# Thermocouple_Test.net
KiCad netlist of a schematic drawn in EAGLE
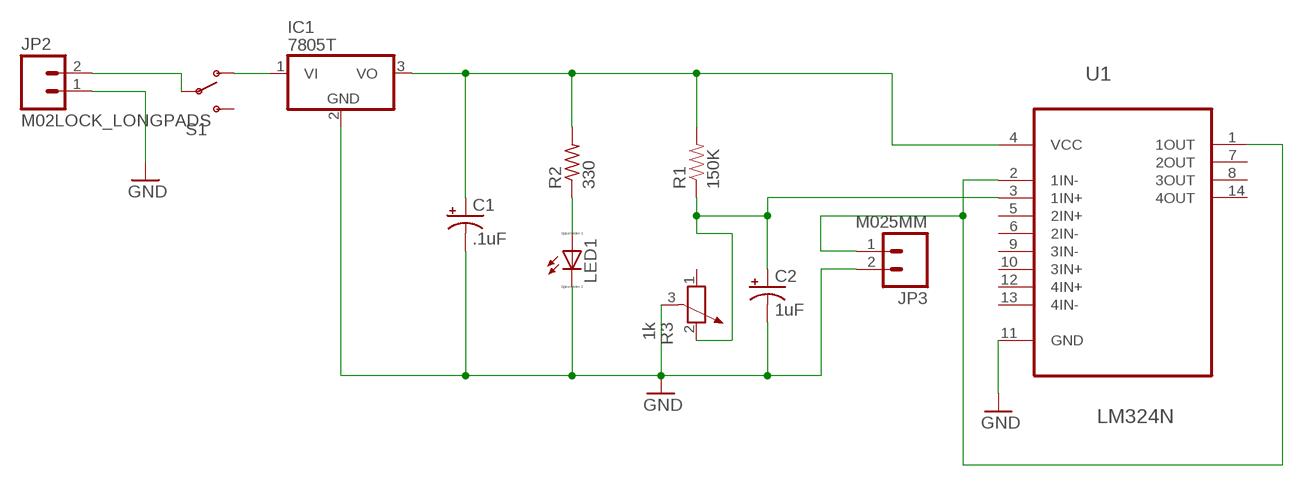
[diagram p0: schematic, sheet 1]

(export (version "E")
  (design (tool "Eeschema 10.0.6"))
  (components
    (comp (ref "C1")
      (value ".1uF")
      (footprint "eagle-import:CPOL-RADIAL-10UF-25V-KIT")
      (libsource (lib "eagle-import") (part "10UF-25V-20%(PTH)KIT"))
    )
    (comp (ref "C2")
      (value "1uF")
      (footprint "eagle-import:CPOL-RADIAL-10UF-25V-KIT")
      (libsource (lib "eagle-import") (part "10UF-25V-20%(PTH)KIT"))
    )
    (comp (ref "IC1")
      (value "7805T")
      (footprint "eagle-import:TO220H")
      (libsource (lib "eagle-import") (part "78T05"))
    )
    (comp (ref "JP2")
      (value "M02LOCK_LONGPADS")
      (footprint "eagle-import:1X02_LOCK_LONGPADS")
      (libsource (lib "eagle-import") (part "M02LOCK_LONGPADS"))
    )
    (comp (ref "JP3")
      (value "M025MM")
      (footprint "eagle-import:SCREWTERMINAL-5MM-2")
      (libsource (lib "eagle-import") (part "M025MM"))
    )
    (comp (ref "LED1")
      (value "LED_ELD260")
      (footprint "eagle-import:LED_LD260")
      (libsource (lib "eagle-import") (part "LED_ELD260"))
    )
    (comp (ref "R1")
      (value "150K")
      (footprint "eagle-import:AXIAL-0.5")
      (libsource (lib "eagle-import") (part "RESISTORPTH-1/2W"))
    )
    (comp (ref "R2")
      (value "330")
      (footprint "eagle-import:0204_7")
      (libsource (lib "eagle-import") (part "R-US_0204/7"))
    )
    (comp (ref "R3")
      (value "1k")
      (footprint "eagle-import:PT-SPIN")
      (libsource (lib "eagle-import") (part "POTENTIOMETER_PT_SPIN"))
    )
    (comp (ref "S1")
      (value "SWITCH-SPDTPTH")
      (footprint "eagle-import:SWITCH-SPDT")
      (libsource (lib "eagle-import") (part "SWITCH-SPDTPTH"))
    )
    (comp (ref "U1")
      (value "LM324N")
      (footprint "eagle-import:DIP254P762X508-14")
      (libsource (lib "eagle-import") (part "LM324N"))
    )
  )
  (nets
    (net (code "1") (name "GND") (class "Default")
      (node (ref "C1") (pin "2") (pinfunction "-_2") (pintype "passive"))
      (node (ref "C2") (pin "2") (pinfunction "-_2") (pintype "passive"))
      (node (ref "IC1") (pin "2") (pinfunction "GND_2") (pintype "passive"))
      (node (ref "JP2") (pin "1") (pinfunction "1_1") (pintype "passive"))
      (node (ref "JP3") (pin "2") (pinfunction "2_2") (pintype "passive"))
      (node (ref "LED1") (pin "K") (pinfunction "C_K") (pintype "passive"))
      (node (ref "R3") (pin "3") (pinfunction "3_3") (pintype "passive"))
      (node (ref "U1") (pin "11") (pinfunction "GND_11") (pintype "passive"))
    )
    (net (code "2") (name "Net-(C1-+)") (class "Default")
      (node (ref "C1") (pin "1") (pinfunction "+_1") (pintype "passive"))
      (node (ref "IC1") (pin "3") (pinfunction "VO_3") (pintype "passive"))
      (node (ref "R1") (pin "P$2") (pinfunction "2_P$2") (pintype "passive"))
      (node (ref "R2") (pin "2") (pinfunction "2_2") (pintype "passive"))
      (node (ref "U1") (pin "4") (pinfunction "VCC_4") (pintype "power_in"))
    )
    (net (code "3") (name "Net-(C2-+)") (class "Default")
      (node (ref "C2") (pin "1") (pinfunction "+_1") (pintype "passive"))
      (node (ref "R1") (pin "P$1") (pinfunction "1_P$1") (pintype "passive"))
      (node (ref "R3") (pin "2") (pinfunction "2_2") (pintype "passive"))
      (node (ref "U1") (pin "3") (pinfunction "1IN+_3") (pintype "input"))
    )
    (net (code "4") (name "Net-(IC1-VI)") (class "Default")
      (node (ref "IC1") (pin "1") (pinfunction "VI_1") (pintype "input"))
      (node (ref "S1") (pin "1") (pinfunction "O_1") (pintype "passive"))
    )
    (net (code "5") (name "Net-(LED1-PadA)") (class "Default")
      (node (ref "LED1") (pin "A") (pinfunction "A_A") (pintype "passive"))
      (node (ref "R2") (pin "1") (pinfunction "1_1") (pintype "passive"))
    )
    (net (code "6") (name "Net-(S1-P)") (class "Default")
      (node (ref "JP2") (pin "2") (pinfunction "2_2") (pintype "passive"))
      (node (ref "S1") (pin "2") (pinfunction "P_2") (pintype "passive"))
    )
    (net (code "7") (name "Net-(U1-1IN-)") (class "Default")
      (node (ref "JP3") (pin "1") (pinfunction "1_1") (pintype "passive"))
      (node (ref "U1") (pin "1") (pinfunction "1OUT_1") (pintype "output"))
      (node (ref "U1") (pin "2") (pinfunction "1IN-_2") (pintype "input"))
    )
    (net (code "8") (name "unconnected-(R3-Pad1)") (class "Default")
      (node (ref "R3") (pin "1") (pinfunction "1_1") (pintype "passive"))
    )
    (net (code "9") (name "unconnected-(S1-S-Pad3)") (class "Default")
      (node (ref "S1") (pin "3") (pinfunction "S_3") (pintype "passive"))
    )
    (net (code "10") (name "unconnected-(U1-2IN+-Pad5)") (class "Default")
      (node (ref "U1") (pin "5") (pinfunction "2IN+_5") (pintype "input"))
    )
    (net (code "11") (name "unconnected-(U1-2IN--Pad6)") (class "Default")
      (node (ref "U1") (pin "6") (pinfunction "2IN-_6") (pintype "input"))
    )
    (net (code "12") (name "unconnected-(U1-2OUT-Pad7)") (class "Default")
      (node (ref "U1") (pin "7") (pinfunction "2OUT_7") (pintype "output"))
    )
    (net (code "13") (name "unconnected-(U1-3IN+-Pad10)") (class "Default")
      (node (ref "U1") (pin "10") (pinfunction "3IN+_10") (pintype "input"))
    )
    (net (code "14") (name "unconnected-(U1-3IN--Pad9)") (class "Default")
      (node (ref "U1") (pin "9") (pinfunction "3IN-_9") (pintype "input"))
    )
    (net (code "15") (name "unconnected-(U1-3OUT-Pad8)") (class "Default")
      (node (ref "U1") (pin "8") (pinfunction "3OUT_8") (pintype "output"))
    )
    (net (code "16") (name "unconnected-(U1-4IN+-Pad12)") (class "Default")
      (node (ref "U1") (pin "12") (pinfunction "4IN+_12") (pintype "input"))
    )
    (net (code "17") (name "unconnected-(U1-4IN--Pad13)") (class "Default")
      (node (ref "U1") (pin "13") (pinfunction "4IN-_13") (pintype "input"))
    )
    (net (code "18") (name "unconnected-(U1-4OUT-Pad14)") (class "Default")
      (node (ref "U1") (pin "14") (pinfunction "4OUT_14") (pintype "output"))
    )
  )
)
